# Ethernet_Sheet2.net
KiCad netlist of a schematic drawn in Altium Designer
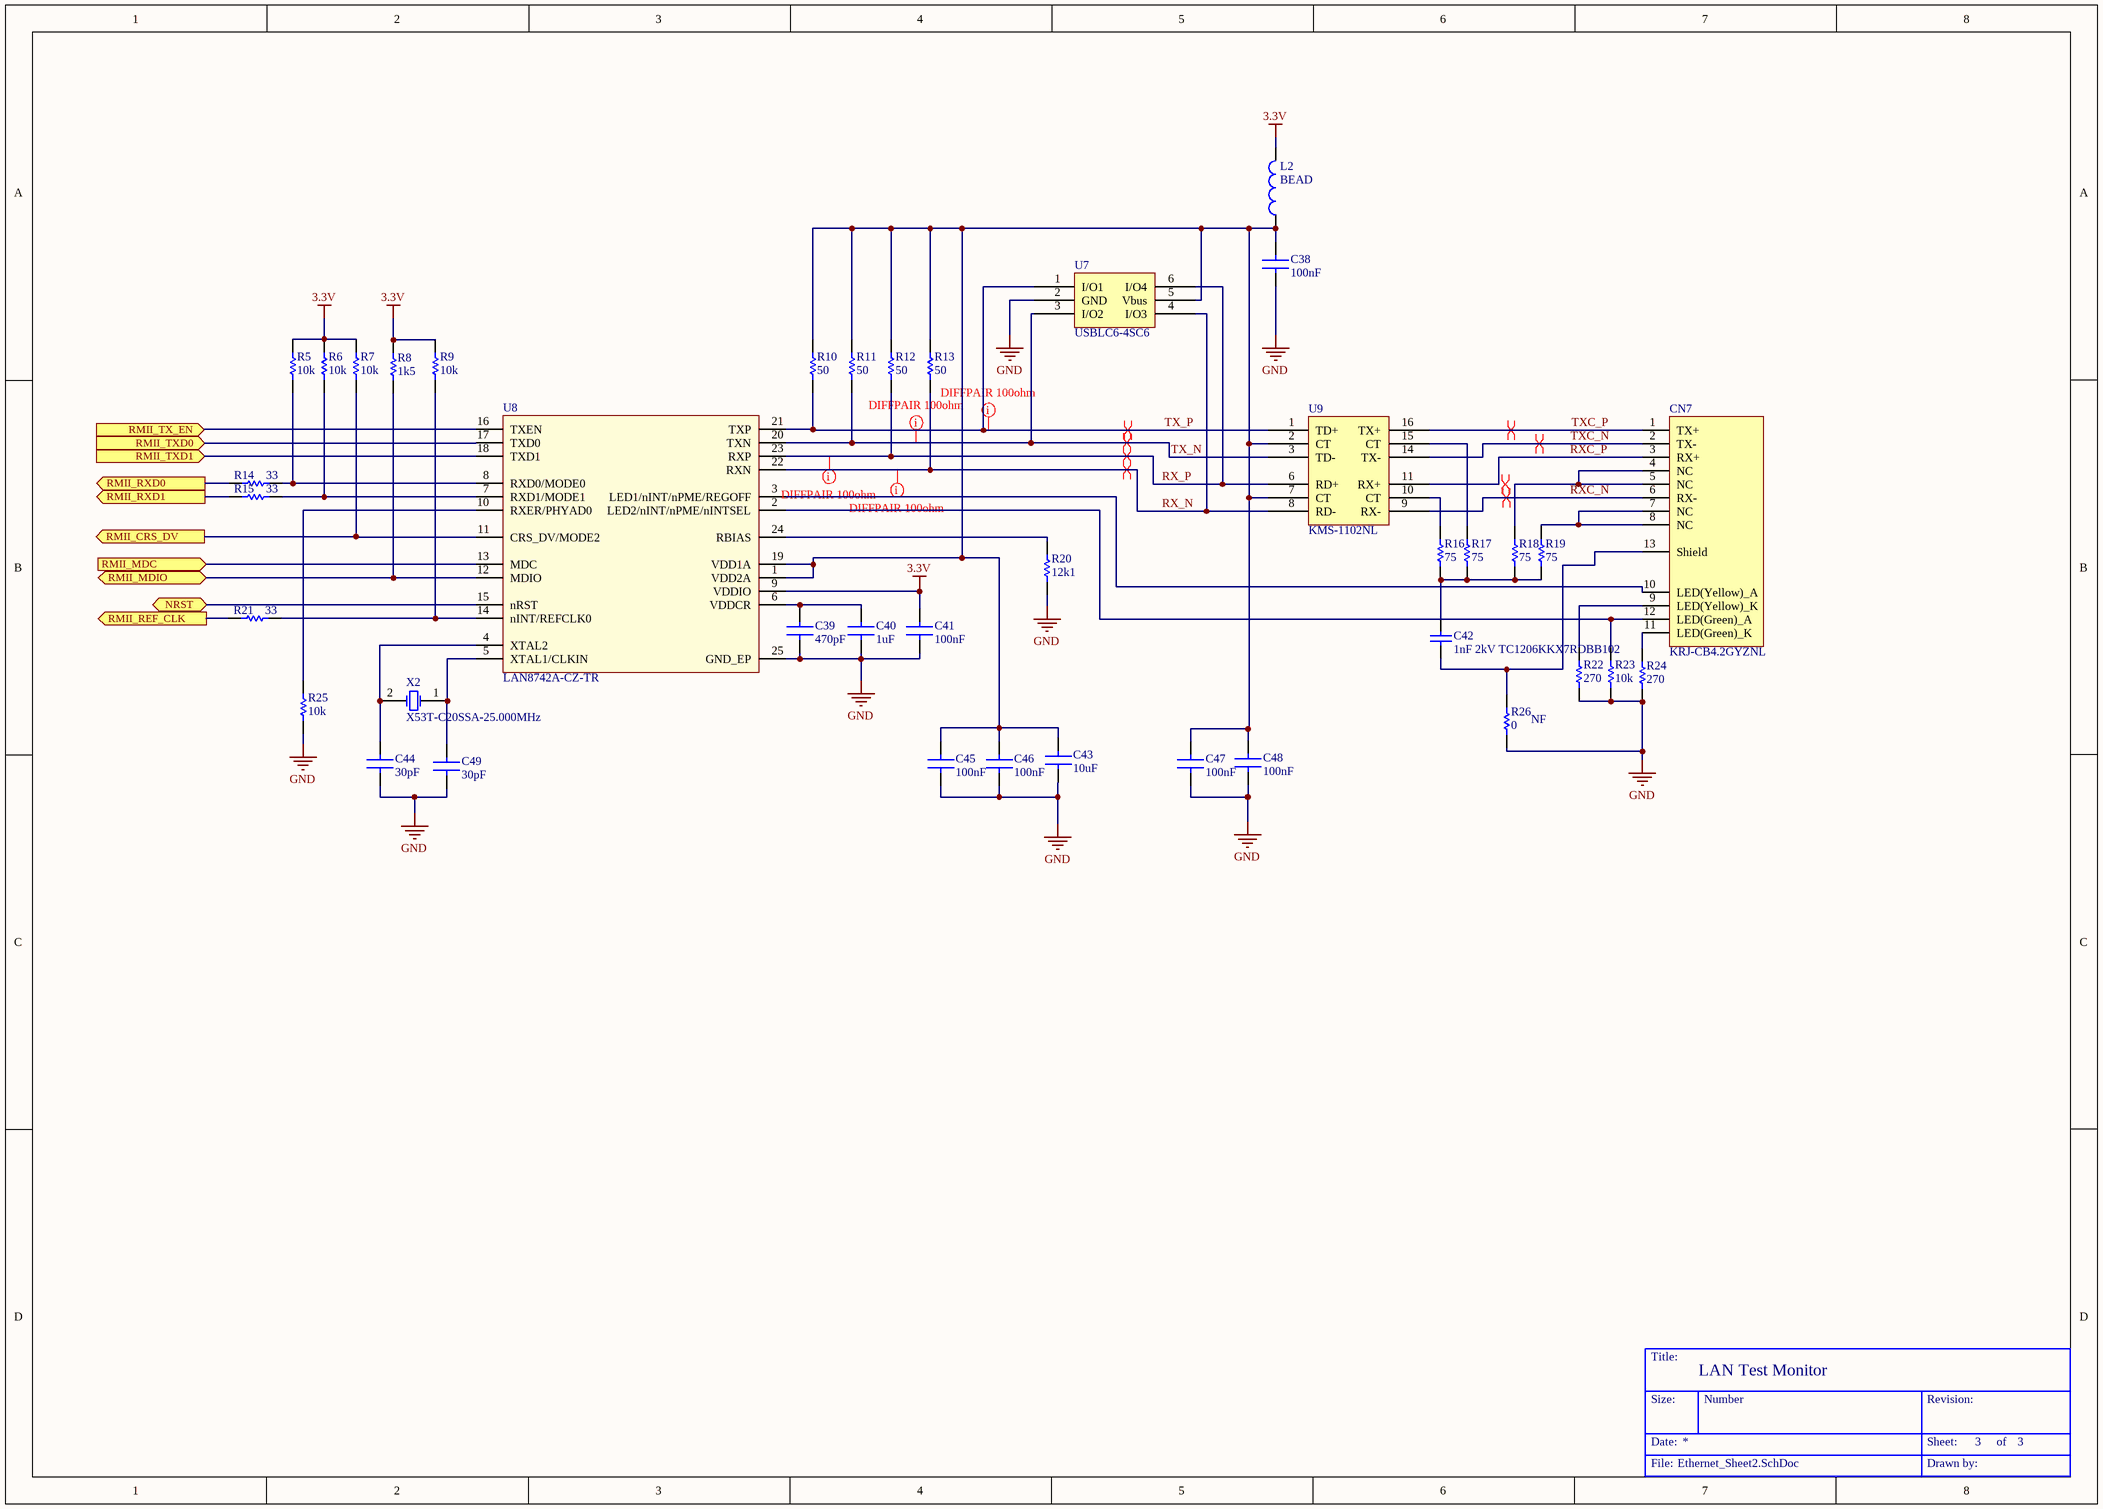
[diagram p0: Ethernet_Sheet2.SchDoc]

(export (version "E")
  (design (tool "Eeschema 10.0.6"))
  (components
    (comp (ref "C38")
      (value "100nF")
      (footprint "Cap_0603")
      (libsource (lib "Schlib1") (part "Cap 100nF 0603 10%"))
    )
    (comp (ref "C39")
      (value "470pF")
      (footprint "Cap_0603")
      (libsource (lib "Schlib1") (part "Cap 470pF 0603 10%"))
    )
    (comp (ref "C40")
      (value "1uF")
      (footprint "Cap_0603")
      (libsource (lib "Schlib1") (part "Cap 1uF 0603 10%"))
    )
    (comp (ref "C41")
      (value "100nF")
      (footprint "Cap_0603")
      (libsource (lib "Schlib1") (part "Cap 100nF 0603 10%"))
    )
    (comp (ref "C42")
      (value "1nF 2kV TC1206KKX7RDBB102")
      (footprint "CAP_1206")
      (description "Capacitor 1nF 2kV")
      (libsource (lib "Schlib1") (part "Cap 1nF 2kV"))
    )
    (comp (ref "C43")
      (value "10uF")
      (footprint "Cap_0603")
      (libsource (lib "Schlib1") (part "Cap 10uF 0603 10%"))
    )
    (comp (ref "C44")
      (value "30pF")
      (footprint "Cap_0603")
      (libsource (lib "Schlib1") (part "Cap 30 pF 0603"))
    )
    (comp (ref "C45")
      (value "100nF")
      (footprint "Cap_0603")
      (libsource (lib "Schlib1") (part "Cap 100nF 0603 10%"))
    )
    (comp (ref "C46")
      (value "100nF")
      (footprint "Cap_0603")
      (libsource (lib "Schlib1") (part "Cap 100nF 0603 10%"))
    )
    (comp (ref "C47")
      (value "100nF")
      (footprint "Cap_0603")
      (libsource (lib "Schlib1") (part "Cap 100nF 0603 10%"))
    )
    (comp (ref "C48")
      (value "100nF")
      (footprint "Cap_0603")
      (libsource (lib "Schlib1") (part "Cap 100nF 0603 10%"))
    )
    (comp (ref "C49")
      (value "30pF")
      (footprint "Cap_0603")
      (libsource (lib "Schlib1") (part "Cap 30 pF 0603"))
    )
    (comp (ref "CN7")
      (value "KRJ-CB4.2GYZNL")
      (footprint "RJ45_KRJ-CB4.2GYZNL")
      (description "100 Base-TX (Fast Ethernet) SMD RJ45 single port (1x1) with LEDS Integrated Magnetics Connector")
      (libsource (lib "Schlib1") (part "KRJ-CB4.2GYZNL"))
    )
    (comp (ref "L2")
      (value "BEAD")
      (footprint "Cap_0603")
      (description "Inductor")
      (fields (field (name "PUBLISHER") "Altium Limited"))
      (libsource (lib "Schlib1") (part "Inductor"))
    )
    (comp (ref "R5")
      (value "10k")
      (footprint "Res_0603")
      (libsource (lib "Schlib1") (part "Res 10k 1% 0603"))
    )
    (comp (ref "R6")
      (value "10k")
      (footprint "Res_0603")
      (libsource (lib "Schlib1") (part "Res 10k 1% 0603"))
    )
    (comp (ref "R7")
      (value "10k")
      (footprint "Res_0603")
      (libsource (lib "Schlib1") (part "Res 10k 1% 0603"))
    )
    (comp (ref "R8")
      (value "1k5")
      (footprint "Res_0603")
      (libsource (lib "Schlib1") (part "Res 1k5 1% 0603"))
    )
    (comp (ref "R9")
      (value "10k")
      (footprint "Res_0603")
      (libsource (lib "Schlib1") (part "Res 10k 1% 0603"))
    )
    (comp (ref "R10") (value "50") (footprint "Res_0603") (libsource (lib "Schlib1") (part "Res 50 1% 0603")))
    (comp (ref "R11") (value "50") (footprint "Res_0603") (libsource (lib "Schlib1") (part "Res 50 1% 0603")))
    (comp (ref "R12") (value "50") (footprint "Res_0603") (libsource (lib "Schlib1") (part "Res 50 1% 0603")))
    (comp (ref "R13") (value "50") (footprint "Res_0603") (libsource (lib "Schlib1") (part "Res 50 1% 0603")))
    (comp (ref "R14") (value "33") (footprint "Res_0603") (libsource (lib "Schlib1") (part "Res 33 1% 0603")))
    (comp (ref "R15") (value "33") (footprint "Res_0603") (libsource (lib "Schlib1") (part "Res 33 1% 0603")))
    (comp (ref "R16") (value "75") (footprint "Res_0603") (libsource (lib "Schlib1") (part "Res 75 1% 0603")))
    (comp (ref "R17") (value "75") (footprint "Res_0603") (libsource (lib "Schlib1") (part "Res 75 1% 0603")))
    (comp (ref "R18") (value "75") (footprint "Res_0603") (libsource (lib "Schlib1") (part "Res 75 1% 0603")))
    (comp (ref "R19") (value "75") (footprint "Res_0603") (libsource (lib "Schlib1") (part "Res 75 1% 0603")))
    (comp (ref "R20")
      (value "12k1")
      (footprint "Res_0603")
      (libsource (lib "Schlib1") (part "Res 12k1 1% 0603"))
    )
    (comp (ref "R21") (value "33") (footprint "Res_0603") (libsource (lib "Schlib1") (part "Res 33 1% 0603")))
    (comp (ref "R22")
      (value "270")
      (footprint "Res_0603")
      (libsource (lib "Schlib1") (part "Res 270 1% 0603"))
    )
    (comp (ref "R23")
      (value "10k")
      (footprint "Res_0603")
      (libsource (lib "Schlib1") (part "Res 10k 1% 0603"))
    )
    (comp (ref "R24")
      (value "270")
      (footprint "Res_0603")
      (libsource (lib "Schlib1") (part "Res 270 1% 0603"))
    )
    (comp (ref "R25")
      (value "10k")
      (footprint "Res_0603")
      (libsource (lib "Schlib1") (part "Res 10k 1% 0603"))
    )
    (comp (ref "R26") (value "0") (footprint "Res_0603") (libsource (lib "Schlib1") (part "Res 0 1% 0603")))
    (comp (ref "U7")
      (value "USBLC6-4SC6")
      (footprint "PcbLib1:SOT23-6L")
      (libsource (lib "Schlib1") (part "USBLC6-4SC6"))
    )
    (comp (ref "U8")
      (value "LAN8742A-CZ-TR")
      (footprint "PcbLib1:QFN24_0R5_4X4")
      (libsource (lib "Schlib1") (part "LAN8742A-CZ-TR"))
    )
    (comp (ref "U9")
      (value "KMS-1102NL")
      (footprint "Trans. KMS-1102NL")
      (libsource (lib "Schlib1") (part "KMS-1102NL_1"))
    )
    (comp (ref "X2")
      (value "X53T-C20SSA-25.000MHz")
      (footprint "PcbLib1:XTAL_2SM_5R0X3R2")
      (description "Crystal Oscillator 25M")
      (fields (field (name "PUBLISHER") "Altium Limited"))
      (libsource (lib "Schlib1") (part "X53T-C20SSA-25.000MHz"))
    )
  )
  (nets
    (net (code "1") (name "/NRST") (class "Default")
      (node (ref "U8") (pin "15") (pinfunction "nRST_15") (pintype "passive"))
    )
    (net (code "2") (name "/RMII_CRS_DV") (class "Default")
      (node (ref "R7") (pin "1") (pinfunction "1_1") (pintype "passive"))
      (node (ref "U8") (pin "11") (pinfunction "CRS_DV/MODE2_11") (pintype "passive"))
    )
    (net (code "3") (name "/RMII_MDC") (class "Default")
      (node (ref "U8") (pin "13") (pinfunction "MDC_13") (pintype "passive"))
    )
    (net (code "4") (name "/RMII_MDIO") (class "Default")
      (node (ref "R8") (pin "2") (pinfunction "2_2") (pintype "passive"))
      (node (ref "U8") (pin "12") (pinfunction "MDIO_12") (pintype "passive"))
    )
    (net (code "5") (name "/RMII_REF_CLK") (class "Default")
      (node (ref "R21") (pin "1") (pinfunction "1_1") (pintype "passive"))
    )
    (net (code "6") (name "/RMII_RXD0") (class "Default")
      (node (ref "R14") (pin "1") (pinfunction "1_1") (pintype "passive"))
    )
    (net (code "7") (name "/RMII_RXD1") (class "Default")
      (node (ref "R15") (pin "1") (pinfunction "1_1") (pintype "passive"))
    )
    (net (code "8") (name "/RMII_TXD0") (class "Default")
      (node (ref "U8") (pin "17") (pinfunction "TXD0_17") (pintype "passive"))
    )
    (net (code "9") (name "/RMII_TXD1") (class "Default")
      (node (ref "U8") (pin "18") (pinfunction "TXD1_18") (pintype "passive"))
    )
    (net (code "10") (name "/RMII_TX_EN") (class "Default")
      (node (ref "U8") (pin "16") (pinfunction "TXEN_16") (pintype "passive"))
    )
    (net (code "11") (name "/RXC_N") (class "Default")
      (node (ref "CN7") (pin "6") (pinfunction "RX-_6") (pintype "passive"))
      (node (ref "U9") (pin "9") (pinfunction "RX-_9") (pintype "passive"))
    )
    (net (code "12") (name "/RXC_P") (class "Default")
      (node (ref "CN7") (pin "3") (pinfunction "RX+_3") (pintype "passive"))
      (node (ref "U9") (pin "11") (pinfunction "RX+_11") (pintype "passive"))
    )
    (net (code "15") (name "/RX_N") (class "Default")
      (node (ref "R13") (pin "1") (pinfunction "1_1") (pintype "passive"))
      (node (ref "U7") (pin "4") (pinfunction "I/O3_4") (pintype "passive"))
      (node (ref "U8") (pin "22") (pinfunction "RXN_22") (pintype "passive"))
      (node (ref "U9") (pin "8") (pinfunction "RD-_8") (pintype "passive"))
    )
    (net (code "16") (name "/RX_P") (class "Default")
      (node (ref "R12") (pin "1") (pinfunction "1_1") (pintype "passive"))
      (node (ref "U7") (pin "6") (pinfunction "I/O4_6") (pintype "passive"))
      (node (ref "U8") (pin "23") (pinfunction "RXP_23") (pintype "passive"))
      (node (ref "U9") (pin "6") (pinfunction "RD+_6") (pintype "passive"))
    )
    (net (code "18") (name "/TXC_N") (class "Default")
      (node (ref "CN7") (pin "2") (pinfunction "TX-_2") (pintype "passive"))
      (node (ref "U9") (pin "14") (pinfunction "TX-_14") (pintype "passive"))
    )
    (net (code "19") (name "/TXC_P") (class "Default")
      (node (ref "CN7") (pin "1") (pinfunction "TX+_1") (pintype "passive"))
      (node (ref "U9") (pin "16") (pinfunction "TX+_16") (pintype "passive"))
    )
    (net (code "20") (name "/TX_N") (class "Default")
      (node (ref "R11") (pin "1") (pinfunction "1_1") (pintype "passive"))
      (node (ref "U7") (pin "3") (pinfunction "I/O2_3") (pintype "passive"))
      (node (ref "U8") (pin "20") (pinfunction "TXN_20") (pintype "passive"))
      (node (ref "U9") (pin "3") (pinfunction "TD-_3") (pintype "passive"))
    )
    (net (code "21") (name "/TX_P") (class "Default")
      (node (ref "R10") (pin "1") (pinfunction "1_1") (pintype "passive"))
      (node (ref "U7") (pin "1") (pinfunction "I/O1_1") (pintype "passive"))
      (node (ref "U8") (pin "21") (pinfunction "TXP_21") (pintype "passive"))
      (node (ref "U9") (pin "1") (pinfunction "TD+_1") (pintype "passive"))
    )
    (net (code "22") (name "3.3V") (class "Default")
      (node (ref "C41") (pin "2") (pinfunction "2_2") (pintype "passive"))
      (node (ref "L2") (pin "2") (pinfunction "2_2") (pintype "passive"))
      (node (ref "R5") (pin "2") (pinfunction "2_2") (pintype "passive"))
      (node (ref "R6") (pin "2") (pinfunction "2_2") (pintype "passive"))
      (node (ref "R7") (pin "2") (pinfunction "2_2") (pintype "passive"))
      (node (ref "R8") (pin "1") (pinfunction "1_1") (pintype "passive"))
      (node (ref "R9") (pin "2") (pinfunction "2_2") (pintype "passive"))
      (node (ref "U8") (pin "9") (pinfunction "VDDIO_9") (pintype "passive"))
    )
    (net (code "23") (name "GND") (class "Default")
      (node (ref "C38") (pin "1") (pinfunction "1_1") (pintype "passive"))
      (node (ref "C39") (pin "1") (pinfunction "1_1") (pintype "passive"))
      (node (ref "C40") (pin "1") (pinfunction "1_1") (pintype "passive"))
      (node (ref "C41") (pin "1") (pinfunction "1_1") (pintype "passive"))
      (node (ref "C43") (pin "1") (pinfunction "1_1") (pintype "passive"))
      (node (ref "C44") (pin "1") (pinfunction "1_1") (pintype "passive"))
      (node (ref "C45") (pin "1") (pinfunction "1_1") (pintype "passive"))
      (node (ref "C46") (pin "1") (pinfunction "1_1") (pintype "passive"))
      (node (ref "C47") (pin "1") (pinfunction "1_1") (pintype "passive"))
      (node (ref "C48") (pin "1") (pinfunction "1_1") (pintype "passive"))
      (node (ref "C49") (pin "1") (pinfunction "1_1") (pintype "passive"))
      (node (ref "R20") (pin "1") (pinfunction "1_1") (pintype "passive"))
      (node (ref "R22") (pin "1") (pinfunction "1_1") (pintype "passive"))
      (node (ref "R23") (pin "1") (pinfunction "1_1") (pintype "passive"))
      (node (ref "R24") (pin "1") (pinfunction "1_1") (pintype "passive"))
      (node (ref "R25") (pin "2") (pinfunction "2_2") (pintype "passive"))
      (node (ref "R26") (pin "1") (pinfunction "1_1") (pintype "passive"))
      (node (ref "U7") (pin "2") (pinfunction "GND_2") (pintype "passive"))
      (node (ref "U8") (pin "25") (pinfunction "GND_EP_25") (pintype "passive"))
    )
    (net (code "24") (name "Net-(C42-Pad2)") (class "Default")
      (node (ref "C42") (pin "2") (pinfunction "2_2") (pintype "passive"))
      (node (ref "R16") (pin "1") (pinfunction "1_1") (pintype "passive"))
      (node (ref "R17") (pin "1") (pinfunction "1_1") (pintype "passive"))
      (node (ref "R18") (pin "1") (pinfunction "1_1") (pintype "passive"))
      (node (ref "R19") (pin "1") (pinfunction "1_1") (pintype "passive"))
    )
    (net (code "25") (name "Net-(CN7-LED(Green)_A)") (class "Default")
      (node (ref "CN7") (pin "12") (pinfunction "LED(Green)_A_12") (pintype "passive"))
      (node (ref "R23") (pin "2") (pinfunction "2_2") (pintype "passive"))
      (node (ref "U8") (pin "2") (pinfunction "LED2/nINT/nPME/nINTSEL_2") (pintype "passive"))
    )
    (net (code "26") (name "Net-(CN7-LED(Green)_K)") (class "Default")
      (node (ref "CN7") (pin "11") (pinfunction "LED(Green)_K_11") (pintype "passive"))
      (node (ref "R24") (pin "2") (pinfunction "2_2") (pintype "passive"))
    )
    (net (code "27") (name "Net-(CN7-LED(Yellow)_A)") (class "Default")
      (node (ref "CN7") (pin "10") (pinfunction "LED(Yellow)_A_10") (pintype "passive"))
      (node (ref "U8") (pin "3") (pinfunction "LED1/nINT/nPME/REGOFF_3") (pintype "passive"))
    )
    (net (code "28") (name "Net-(CN7-LED(Yellow)_K)") (class "Default")
      (node (ref "CN7") (pin "9") (pinfunction "LED(Yellow)_K_9") (pintype "passive"))
      (node (ref "R22") (pin "2") (pinfunction "2_2") (pintype "passive"))
    )
    (net (code "29") (name "Net-(CN7-NC-Pad4)") (class "Default")
      (node (ref "CN7") (pin "4") (pinfunction "NC_4") (pintype "passive"))
      (node (ref "CN7") (pin "5") (pinfunction "NC_5") (pintype "passive"))
      (node (ref "R18") (pin "2") (pinfunction "2_2") (pintype "passive"))
    )
    (net (code "30") (name "Net-(CN7-NC-Pad7)") (class "Default")
      (node (ref "CN7") (pin "7") (pinfunction "NC_7") (pintype "passive"))
      (node (ref "CN7") (pin "8") (pinfunction "NC_8") (pintype "passive"))
      (node (ref "R19") (pin "2") (pinfunction "2_2") (pintype "passive"))
    )
    (net (code "31") (name "Net-(CN7-Shield)") (class "Default")
      (node (ref "C42") (pin "1") (pinfunction "1_1") (pintype "passive"))
      (node (ref "CN7") (pin "13") (pinfunction "Shield_13") (pintype "passive"))
      (node (ref "R26") (pin "2") (pinfunction "2_2") (pintype "passive"))
    )
    (net (code "32") (name "Net-(R16-Pad2)") (class "Default")
      (node (ref "R16") (pin "2") (pinfunction "2_2") (pintype "passive"))
      (node (ref "U9") (pin "10") (pinfunction "CT_10") (pintype "passive"))
    )
    (net (code "33") (name "Net-(R17-Pad2)") (class "Default")
      (node (ref "R17") (pin "2") (pinfunction "2_2") (pintype "passive"))
      (node (ref "U9") (pin "15") (pinfunction "CT_15") (pintype "passive"))
    )
    (net (code "34") (name "Net-(U7-Vbus)") (class "Default")
      (node (ref "C38") (pin "2") (pinfunction "2_2") (pintype "passive"))
      (node (ref "C43") (pin "2") (pinfunction "2_2") (pintype "passive"))
      (node (ref "C45") (pin "2") (pinfunction "2_2") (pintype "passive"))
      (node (ref "C46") (pin "2") (pinfunction "2_2") (pintype "passive"))
      (node (ref "C47") (pin "2") (pinfunction "2_2") (pintype "passive"))
      (node (ref "C48") (pin "2") (pinfunction "2_2") (pintype "passive"))
      (node (ref "L2") (pin "1") (pinfunction "1_1") (pintype "passive"))
      (node (ref "R10") (pin "2") (pinfunction "2_2") (pintype "passive"))
      (node (ref "R11") (pin "2") (pinfunction "2_2") (pintype "passive"))
      (node (ref "R12") (pin "2") (pinfunction "2_2") (pintype "passive"))
      (node (ref "R13") (pin "2") (pinfunction "2_2") (pintype "passive"))
      (node (ref "U7") (pin "5") (pinfunction "Vbus_5") (pintype "passive"))
      (node (ref "U8") (pin "1") (pinfunction "VDD2A_1") (pintype "passive"))
      (node (ref "U8") (pin "19") (pinfunction "VDD1A_19") (pintype "passive"))
      (node (ref "U9") (pin "2") (pinfunction "CT_2") (pintype "passive"))
      (node (ref "U9") (pin "7") (pinfunction "CT_7") (pintype "passive"))
    )
    (net (code "35") (name "Net-(U8-RBIAS)") (class "Default")
      (node (ref "R20") (pin "2") (pinfunction "2_2") (pintype "passive"))
      (node (ref "U8") (pin "24") (pinfunction "RBIAS_24") (pintype "passive"))
    )
    (net (code "36") (name "Net-(U8-RXD0{slash}MODE0)") (class "Default")
      (node (ref "R14") (pin "2") (pinfunction "2_2") (pintype "passive"))
      (node (ref "R5") (pin "1") (pinfunction "1_1") (pintype "passive"))
      (node (ref "U8") (pin "8") (pinfunction "RXD0/MODE0_8") (pintype "passive"))
    )
    (net (code "37") (name "Net-(U8-RXD1{slash}MODE1)") (class "Default")
      (node (ref "R15") (pin "2") (pinfunction "2_2") (pintype "passive"))
      (node (ref "R6") (pin "1") (pinfunction "1_1") (pintype "passive"))
      (node (ref "U8") (pin "7") (pinfunction "RXD1/MODE1_7") (pintype "passive"))
    )
    (net (code "38") (name "Net-(U8-RXER{slash}PHYAD0)") (class "Default")
      (node (ref "R25") (pin "1") (pinfunction "1_1") (pintype "passive"))
      (node (ref "U8") (pin "10") (pinfunction "RXER/PHYAD0_10") (pintype "passive"))
    )
    (net (code "39") (name "Net-(U8-VDDCR)") (class "Default")
      (node (ref "C39") (pin "2") (pinfunction "2_2") (pintype "passive"))
      (node (ref "C40") (pin "2") (pinfunction "2_2") (pintype "passive"))
      (node (ref "U8") (pin "6") (pinfunction "VDDCR_6") (pintype "passive"))
    )
    (net (code "40") (name "Net-(U8-XTAL1{slash}CLKIN)") (class "Default")
      (node (ref "C49") (pin "2") (pinfunction "2_2") (pintype "passive"))
      (node (ref "U8") (pin "5") (pinfunction "XTAL1/CLKIN_5") (pintype "passive"))
      (node (ref "X2") (pin "1") (pinfunction "OSC1_1") (pintype "passive"))
    )
    (net (code "41") (name "Net-(U8-XTAL2)") (class "Default")
      (node (ref "C44") (pin "2") (pinfunction "2_2") (pintype "passive"))
      (node (ref "U8") (pin "4") (pinfunction "XTAL2_4") (pintype "passive"))
      (node (ref "X2") (pin "2") (pinfunction "OSC2_2") (pintype "passive"))
    )
    (net (code "42") (name "Net-(U8-nINT{slash}REFCLK0)") (class "Default")
      (node (ref "R21") (pin "2") (pinfunction "2_2") (pintype "passive"))
      (node (ref "R9") (pin "1") (pinfunction "1_1") (pintype "passive"))
      (node (ref "U8") (pin "14") (pinfunction "nINT/REFCLK0_14") (pintype "passive"))
    )
  )
)
